# AddOnCard.net
KiCad netlist of a schematic drawn in Altium Designer
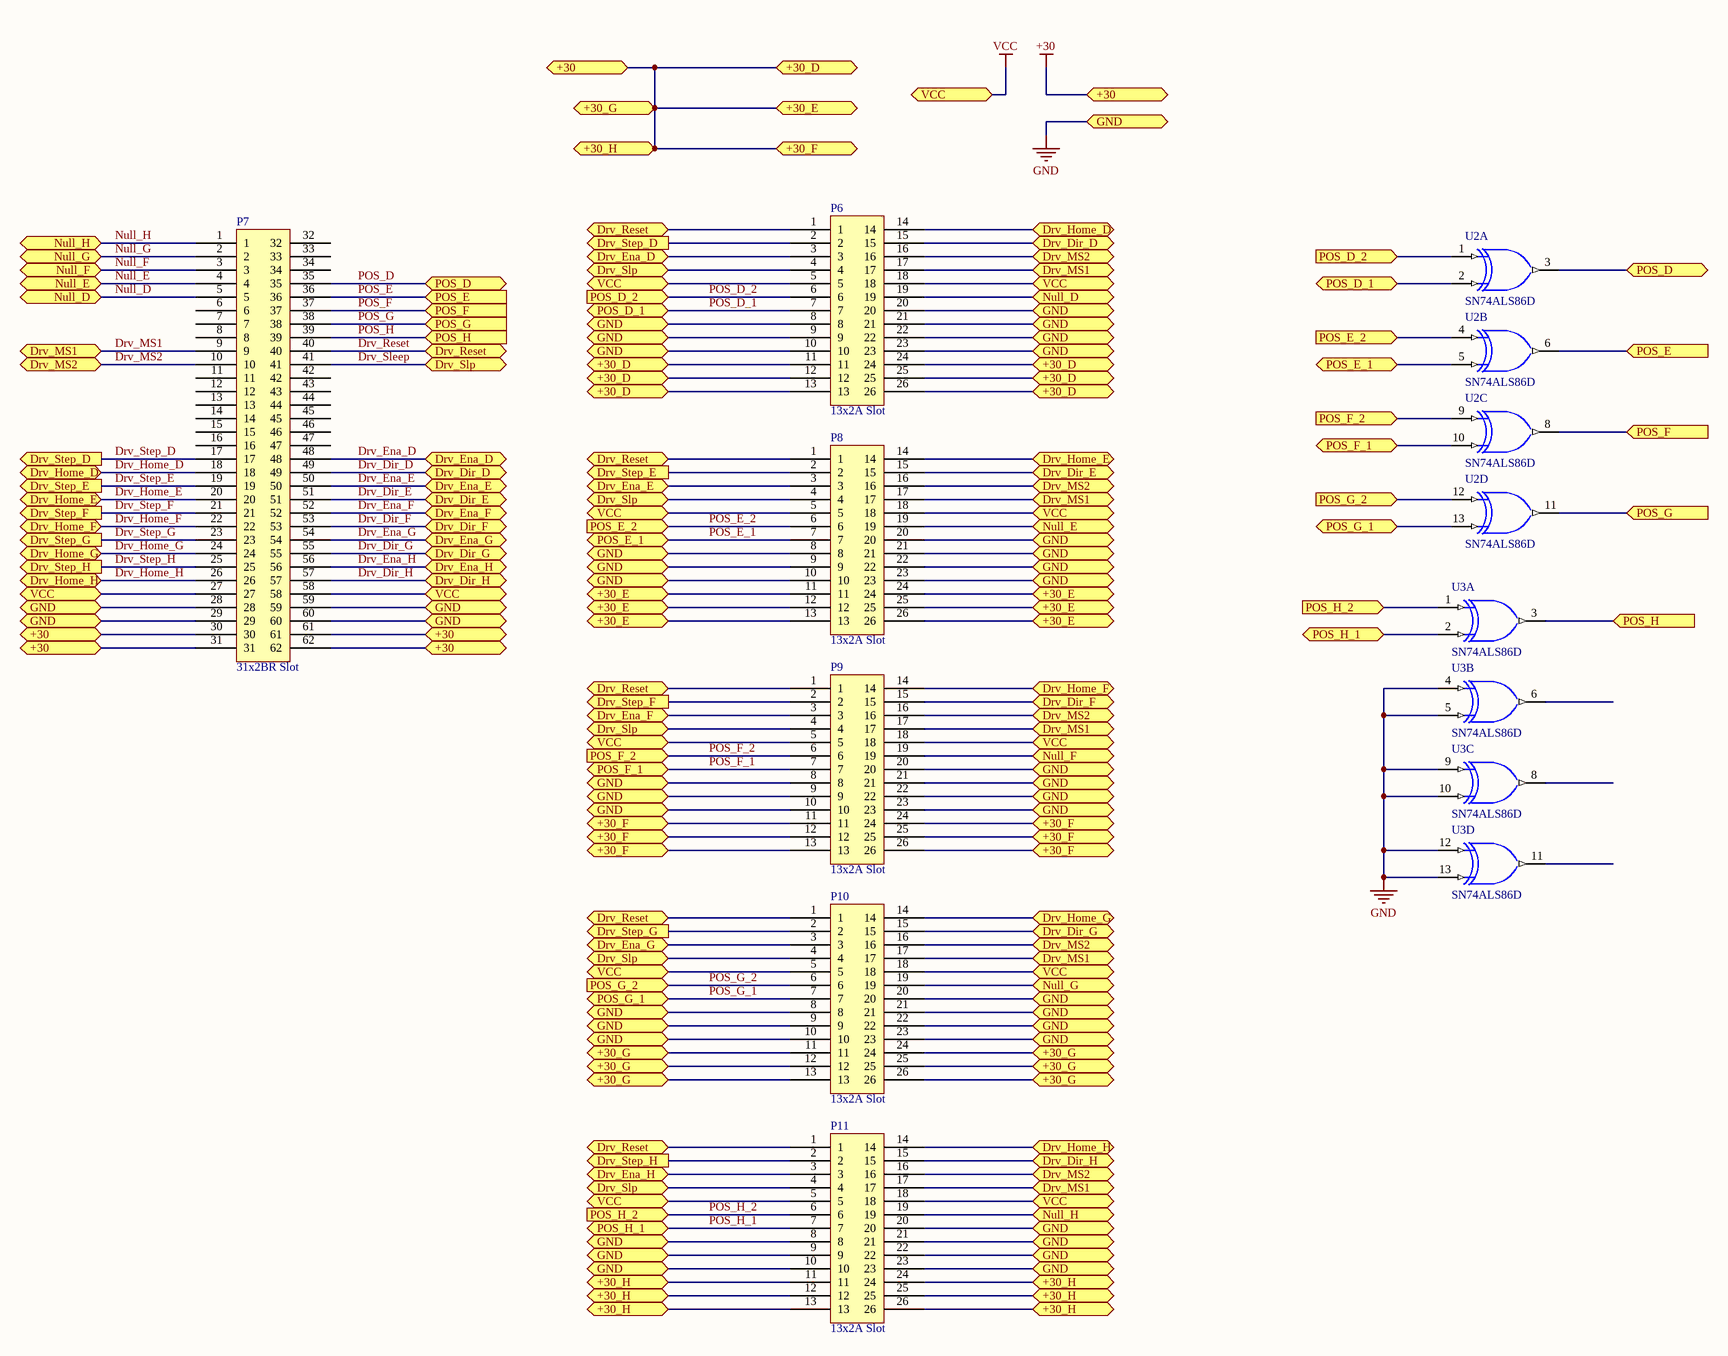
[diagram p0: AddOnCard.SchDoc]

(export (version "E")
  (design (tool "Eeschema 10.0.6"))
  (components
    (comp (ref "P6") (value "13x2A Slot") (footprint "SL-26A") (libsource (lib "Slot") (part "13x2A Slot")))
    (comp (ref "P7")
      (value "31x2BR Slot")
      (footprint "SL-62BR")
      (description "31x2 Slot")
      (libsource (lib "Slot") (part "31x2BR Slot"))
    )
    (comp (ref "P8") (value "13x2A Slot") (footprint "SL-26A") (libsource (lib "Slot") (part "13x2A Slot")))
    (comp (ref "P9") (value "13x2A Slot") (footprint "SL-26A") (libsource (lib "Slot") (part "13x2A Slot")))
    (comp (ref "P10") (value "13x2A Slot") (footprint "SL-26A") (libsource (lib "Slot") (part "13x2A Slot")))
    (comp (ref "P11") (value "13x2A Slot") (footprint "SL-26A") (libsource (lib "Slot") (part "13x2A Slot")))
    (comp (ref "U2")
      (value "SN74ALS86D")
      (footprint "D014_N")
      (description "Quadruple 2-Input Exclusive-OR Gate")
      (fields (field (name "PUBLISHER") "Altium Limited"))
      (libsource (lib "TI Logic Gate 1") (part "SN74ALS86D"))
    )
    (comp (ref "U3")
      (value "SN74ALS86D")
      (footprint "D014_N")
      (description "Quadruple 2-Input Exclusive-OR Gate")
      (fields (field (name "PUBLISHER") "Altium Limited"))
      (libsource (lib "TI Logic Gate 1") (part "SN74ALS86D"))
    )
  )
  (nets
    (net (code "1") (name "+30") (class "Default")
      (node (ref "P10") (pin "11") (pinfunction "11_11") (pintype "passive"))
      (node (ref "P10") (pin "12") (pinfunction "12_12") (pintype "passive"))
      (node (ref "P10") (pin "13") (pinfunction "13_13") (pintype "passive"))
      (node (ref "P10") (pin "24") (pinfunction "24_24") (pintype "passive"))
      (node (ref "P10") (pin "25") (pinfunction "25_25") (pintype "passive"))
      (node (ref "P10") (pin "26") (pinfunction "26_26") (pintype "passive"))
      (node (ref "P11") (pin "11") (pinfunction "11_11") (pintype "passive"))
      (node (ref "P11") (pin "12") (pinfunction "12_12") (pintype "passive"))
      (node (ref "P11") (pin "13") (pinfunction "13_13") (pintype "passive"))
      (node (ref "P11") (pin "24") (pinfunction "24_24") (pintype "passive"))
      (node (ref "P11") (pin "25") (pinfunction "25_25") (pintype "passive"))
      (node (ref "P11") (pin "26") (pinfunction "26_26") (pintype "passive"))
      (node (ref "P6") (pin "11") (pinfunction "11_11") (pintype "passive"))
      (node (ref "P6") (pin "12") (pinfunction "12_12") (pintype "passive"))
      (node (ref "P6") (pin "13") (pinfunction "13_13") (pintype "passive"))
      (node (ref "P6") (pin "24") (pinfunction "24_24") (pintype "passive"))
      (node (ref "P6") (pin "25") (pinfunction "25_25") (pintype "passive"))
      (node (ref "P6") (pin "26") (pinfunction "26_26") (pintype "passive"))
      (node (ref "P7") (pin "30") (pinfunction "30_30") (pintype "passive"))
      (node (ref "P7") (pin "31") (pinfunction "31_31") (pintype "passive"))
      (node (ref "P7") (pin "61") (pinfunction "61_61") (pintype "passive"))
      (node (ref "P7") (pin "62") (pinfunction "62_62") (pintype "passive"))
      (node (ref "P8") (pin "11") (pinfunction "11_11") (pintype "passive"))
      (node (ref "P8") (pin "12") (pinfunction "12_12") (pintype "passive"))
      (node (ref "P8") (pin "13") (pinfunction "13_13") (pintype "passive"))
      (node (ref "P8") (pin "24") (pinfunction "24_24") (pintype "passive"))
      (node (ref "P8") (pin "25") (pinfunction "25_25") (pintype "passive"))
      (node (ref "P8") (pin "26") (pinfunction "26_26") (pintype "passive"))
      (node (ref "P9") (pin "11") (pinfunction "11_11") (pintype "passive"))
      (node (ref "P9") (pin "12") (pinfunction "12_12") (pintype "passive"))
      (node (ref "P9") (pin "13") (pinfunction "13_13") (pintype "passive"))
      (node (ref "P9") (pin "24") (pinfunction "24_24") (pintype "passive"))
      (node (ref "P9") (pin "25") (pinfunction "25_25") (pintype "passive"))
      (node (ref "P9") (pin "26") (pinfunction "26_26") (pintype "passive"))
    )
    (net (code "2") (name "/Drv_Dir_D") (class "Default")
      (node (ref "P6") (pin "15") (pinfunction "15_15") (pintype "passive"))
      (node (ref "P7") (pin "49") (pinfunction "49_49") (pintype "passive"))
    )
    (net (code "3") (name "/Drv_Dir_E") (class "Default")
      (node (ref "P7") (pin "51") (pinfunction "51_51") (pintype "passive"))
      (node (ref "P8") (pin "15") (pinfunction "15_15") (pintype "passive"))
    )
    (net (code "4") (name "/Drv_Dir_F") (class "Default")
      (node (ref "P7") (pin "53") (pinfunction "53_53") (pintype "passive"))
      (node (ref "P9") (pin "15") (pinfunction "15_15") (pintype "passive"))
    )
    (net (code "5") (name "/Drv_Dir_G") (class "Default")
      (node (ref "P10") (pin "15") (pinfunction "15_15") (pintype "passive"))
      (node (ref "P7") (pin "55") (pinfunction "55_55") (pintype "passive"))
    )
    (net (code "6") (name "/Drv_Dir_H") (class "Default")
      (node (ref "P11") (pin "15") (pinfunction "15_15") (pintype "passive"))
      (node (ref "P7") (pin "57") (pinfunction "57_57") (pintype "passive"))
    )
    (net (code "7") (name "/Drv_Ena_D") (class "Default")
      (node (ref "P6") (pin "3") (pinfunction "3_3") (pintype "passive"))
      (node (ref "P7") (pin "48") (pinfunction "48_48") (pintype "passive"))
    )
    (net (code "8") (name "/Drv_Ena_E") (class "Default")
      (node (ref "P7") (pin "50") (pinfunction "50_50") (pintype "passive"))
      (node (ref "P8") (pin "3") (pinfunction "3_3") (pintype "passive"))
    )
    (net (code "9") (name "/Drv_Ena_F") (class "Default")
      (node (ref "P7") (pin "52") (pinfunction "52_52") (pintype "passive"))
      (node (ref "P9") (pin "3") (pinfunction "3_3") (pintype "passive"))
    )
    (net (code "10") (name "/Drv_Ena_G") (class "Default")
      (node (ref "P10") (pin "3") (pinfunction "3_3") (pintype "passive"))
      (node (ref "P7") (pin "54") (pinfunction "54_54") (pintype "passive"))
    )
    (net (code "11") (name "/Drv_Ena_H") (class "Default")
      (node (ref "P11") (pin "3") (pinfunction "3_3") (pintype "passive"))
      (node (ref "P7") (pin "56") (pinfunction "56_56") (pintype "passive"))
    )
    (net (code "12") (name "/Drv_Home_D") (class "Default")
      (node (ref "P6") (pin "14") (pinfunction "14_14") (pintype "passive"))
      (node (ref "P7") (pin "18") (pinfunction "18_18") (pintype "passive"))
    )
    (net (code "13") (name "/Drv_Home_E") (class "Default")
      (node (ref "P7") (pin "20") (pinfunction "20_20") (pintype "passive"))
      (node (ref "P8") (pin "14") (pinfunction "14_14") (pintype "passive"))
    )
    (net (code "14") (name "/Drv_Home_F") (class "Default")
      (node (ref "P7") (pin "22") (pinfunction "22_22") (pintype "passive"))
      (node (ref "P9") (pin "14") (pinfunction "14_14") (pintype "passive"))
    )
    (net (code "15") (name "/Drv_Home_G") (class "Default")
      (node (ref "P10") (pin "14") (pinfunction "14_14") (pintype "passive"))
      (node (ref "P7") (pin "24") (pinfunction "24_24") (pintype "passive"))
    )
    (net (code "16") (name "/Drv_Home_H") (class "Default")
      (node (ref "P11") (pin "14") (pinfunction "14_14") (pintype "passive"))
      (node (ref "P7") (pin "26") (pinfunction "26_26") (pintype "passive"))
    )
    (net (code "17") (name "/Drv_MS1") (class "Default")
      (node (ref "P10") (pin "17") (pinfunction "17_17") (pintype "passive"))
      (node (ref "P11") (pin "17") (pinfunction "17_17") (pintype "passive"))
      (node (ref "P6") (pin "17") (pinfunction "17_17") (pintype "passive"))
      (node (ref "P7") (pin "9") (pinfunction "9_9") (pintype "passive"))
      (node (ref "P8") (pin "17") (pinfunction "17_17") (pintype "passive"))
      (node (ref "P9") (pin "17") (pinfunction "17_17") (pintype "passive"))
    )
    (net (code "18") (name "/Drv_MS2") (class "Default")
      (node (ref "P10") (pin "16") (pinfunction "16_16") (pintype "passive"))
      (node (ref "P11") (pin "16") (pinfunction "16_16") (pintype "passive"))
      (node (ref "P6") (pin "16") (pinfunction "16_16") (pintype "passive"))
      (node (ref "P7") (pin "10") (pinfunction "10_10") (pintype "passive"))
      (node (ref "P8") (pin "16") (pinfunction "16_16") (pintype "passive"))
      (node (ref "P9") (pin "16") (pinfunction "16_16") (pintype "passive"))
    )
    (net (code "19") (name "/Drv_Reset") (class "Default")
      (node (ref "P10") (pin "1") (pinfunction "1_1") (pintype "passive"))
      (node (ref "P11") (pin "1") (pinfunction "1_1") (pintype "passive"))
      (node (ref "P6") (pin "1") (pinfunction "1_1") (pintype "passive"))
      (node (ref "P7") (pin "40") (pinfunction "40_40") (pintype "passive"))
      (node (ref "P8") (pin "1") (pinfunction "1_1") (pintype "passive"))
      (node (ref "P9") (pin "1") (pinfunction "1_1") (pintype "passive"))
    )
    (net (code "20") (name "/Drv_Sleep") (class "Default")
      (node (ref "P10") (pin "4") (pinfunction "4_4") (pintype "passive"))
      (node (ref "P11") (pin "4") (pinfunction "4_4") (pintype "passive"))
      (node (ref "P6") (pin "4") (pinfunction "4_4") (pintype "passive"))
      (node (ref "P7") (pin "41") (pinfunction "41_41") (pintype "passive"))
      (node (ref "P8") (pin "4") (pinfunction "4_4") (pintype "passive"))
      (node (ref "P9") (pin "4") (pinfunction "4_4") (pintype "passive"))
    )
    (net (code "21") (name "/Drv_Step_D") (class "Default")
      (node (ref "P6") (pin "2") (pinfunction "2_2") (pintype "passive"))
      (node (ref "P7") (pin "17") (pinfunction "17_17") (pintype "passive"))
    )
    (net (code "22") (name "/Drv_Step_E") (class "Default")
      (node (ref "P7") (pin "19") (pinfunction "19_19") (pintype "passive"))
      (node (ref "P8") (pin "2") (pinfunction "2_2") (pintype "passive"))
    )
    (net (code "23") (name "/Drv_Step_F") (class "Default")
      (node (ref "P7") (pin "21") (pinfunction "21_21") (pintype "passive"))
      (node (ref "P9") (pin "2") (pinfunction "2_2") (pintype "passive"))
    )
    (net (code "24") (name "/Drv_Step_G") (class "Default")
      (node (ref "P10") (pin "2") (pinfunction "2_2") (pintype "passive"))
      (node (ref "P7") (pin "23") (pinfunction "23_23") (pintype "passive"))
    )
    (net (code "25") (name "/Drv_Step_H") (class "Default")
      (node (ref "P11") (pin "2") (pinfunction "2_2") (pintype "passive"))
      (node (ref "P7") (pin "25") (pinfunction "25_25") (pintype "passive"))
    )
    (net (code "26") (name "/Null_D") (class "Default")
      (node (ref "P6") (pin "19") (pinfunction "19_19") (pintype "passive"))
      (node (ref "P7") (pin "5") (pinfunction "5_5") (pintype "passive"))
    )
    (net (code "27") (name "/Null_E") (class "Default")
      (node (ref "P7") (pin "4") (pinfunction "4_4") (pintype "passive"))
      (node (ref "P8") (pin "19") (pinfunction "19_19") (pintype "passive"))
    )
    (net (code "28") (name "/Null_F") (class "Default")
      (node (ref "P7") (pin "3") (pinfunction "3_3") (pintype "passive"))
      (node (ref "P9") (pin "19") (pinfunction "19_19") (pintype "passive"))
    )
    (net (code "29") (name "/Null_G") (class "Default")
      (node (ref "P10") (pin "19") (pinfunction "19_19") (pintype "passive"))
      (node (ref "P7") (pin "2") (pinfunction "2_2") (pintype "passive"))
    )
    (net (code "30") (name "/Null_H") (class "Default")
      (node (ref "P11") (pin "19") (pinfunction "19_19") (pintype "passive"))
      (node (ref "P7") (pin "1") (pinfunction "1_1") (pintype "passive"))
    )
    (net (code "31") (name "/POS_D") (class "Default")
      (node (ref "P7") (pin "35") (pinfunction "35_35") (pintype "passive"))
      (node (ref "U2") (pin "3") (pinfunction "Y_3") (pintype "output"))
    )
    (net (code "32") (name "/POS_D_1") (class "Default")
      (node (ref "P6") (pin "7") (pinfunction "7_7") (pintype "passive"))
      (node (ref "U2") (pin "2") (pinfunction "B_2") (pintype "input"))
    )
    (net (code "33") (name "/POS_D_2") (class "Default")
      (node (ref "P6") (pin "6") (pinfunction "6_6") (pintype "passive"))
      (node (ref "U2") (pin "1") (pinfunction "A_1") (pintype "input"))
    )
    (net (code "34") (name "/POS_E") (class "Default")
      (node (ref "P7") (pin "36") (pinfunction "36_36") (pintype "passive"))
      (node (ref "U2") (pin "6") (pinfunction "Y_6") (pintype "output"))
    )
    (net (code "35") (name "/POS_E_1") (class "Default")
      (node (ref "P8") (pin "7") (pinfunction "7_7") (pintype "passive"))
      (node (ref "U2") (pin "5") (pinfunction "B_5") (pintype "input"))
    )
    (net (code "36") (name "/POS_E_2") (class "Default")
      (node (ref "P8") (pin "6") (pinfunction "6_6") (pintype "passive"))
      (node (ref "U2") (pin "4") (pinfunction "A_4") (pintype "input"))
    )
    (net (code "37") (name "/POS_F") (class "Default")
      (node (ref "P7") (pin "37") (pinfunction "37_37") (pintype "passive"))
      (node (ref "U2") (pin "8") (pinfunction "Y_8") (pintype "output"))
    )
    (net (code "38") (name "/POS_F_1") (class "Default")
      (node (ref "P9") (pin "7") (pinfunction "7_7") (pintype "passive"))
      (node (ref "U2") (pin "10") (pinfunction "B_10") (pintype "input"))
    )
    (net (code "39") (name "/POS_F_2") (class "Default")
      (node (ref "P9") (pin "6") (pinfunction "6_6") (pintype "passive"))
      (node (ref "U2") (pin "9") (pinfunction "A_9") (pintype "input"))
    )
    (net (code "40") (name "/POS_G") (class "Default")
      (node (ref "P7") (pin "38") (pinfunction "38_38") (pintype "passive"))
      (node (ref "U2") (pin "11") (pinfunction "Y_11") (pintype "output"))
    )
    (net (code "41") (name "/POS_G_1") (class "Default")
      (node (ref "P10") (pin "7") (pinfunction "7_7") (pintype "passive"))
      (node (ref "U2") (pin "13") (pinfunction "B_13") (pintype "input"))
    )
    (net (code "42") (name "/POS_G_2") (class "Default")
      (node (ref "P10") (pin "6") (pinfunction "6_6") (pintype "passive"))
      (node (ref "U2") (pin "12") (pinfunction "A_12") (pintype "input"))
    )
    (net (code "43") (name "/POS_H") (class "Default")
      (node (ref "P7") (pin "39") (pinfunction "39_39") (pintype "passive"))
      (node (ref "U3") (pin "3") (pinfunction "Y_3") (pintype "output"))
    )
    (net (code "44") (name "/POS_H_1") (class "Default")
      (node (ref "P11") (pin "7") (pinfunction "7_7") (pintype "passive"))
      (node (ref "U3") (pin "2") (pinfunction "B_2") (pintype "input"))
    )
    (net (code "45") (name "/POS_H_2") (class "Default")
      (node (ref "P11") (pin "6") (pinfunction "6_6") (pintype "passive"))
      (node (ref "U3") (pin "1") (pinfunction "A_1") (pintype "input"))
    )
    (net (code "46") (name "GND") (class "Default")
      (node (ref "P10") (pin "10") (pinfunction "10_10") (pintype "passive"))
      (node (ref "P10") (pin "20") (pinfunction "20_20") (pintype "passive"))
      (node (ref "P10") (pin "21") (pinfunction "21_21") (pintype "passive"))
      (node (ref "P10") (pin "22") (pinfunction "22_22") (pintype "passive"))
      (node (ref "P10") (pin "23") (pinfunction "23_23") (pintype "passive"))
      (node (ref "P10") (pin "8") (pinfunction "8_8") (pintype "passive"))
      (node (ref "P10") (pin "9") (pinfunction "9_9") (pintype "passive"))
      (node (ref "P11") (pin "10") (pinfunction "10_10") (pintype "passive"))
      (node (ref "P11") (pin "20") (pinfunction "20_20") (pintype "passive"))
      (node (ref "P11") (pin "21") (pinfunction "21_21") (pintype "passive"))
      (node (ref "P11") (pin "22") (pinfunction "22_22") (pintype "passive"))
      (node (ref "P11") (pin "23") (pinfunction "23_23") (pintype "passive"))
      (node (ref "P11") (pin "8") (pinfunction "8_8") (pintype "passive"))
      (node (ref "P11") (pin "9") (pinfunction "9_9") (pintype "passive"))
      (node (ref "P6") (pin "10") (pinfunction "10_10") (pintype "passive"))
      (node (ref "P6") (pin "20") (pinfunction "20_20") (pintype "passive"))
      (node (ref "P6") (pin "21") (pinfunction "21_21") (pintype "passive"))
      (node (ref "P6") (pin "22") (pinfunction "22_22") (pintype "passive"))
      (node (ref "P6") (pin "23") (pinfunction "23_23") (pintype "passive"))
      (node (ref "P6") (pin "8") (pinfunction "8_8") (pintype "passive"))
      (node (ref "P6") (pin "9") (pinfunction "9_9") (pintype "passive"))
      (node (ref "P7") (pin "28") (pinfunction "28_28") (pintype "passive"))
      (node (ref "P7") (pin "29") (pinfunction "29_29") (pintype "passive"))
      (node (ref "P7") (pin "59") (pinfunction "59_59") (pintype "passive"))
      (node (ref "P7") (pin "60") (pinfunction "60_60") (pintype "passive"))
      (node (ref "P8") (pin "10") (pinfunction "10_10") (pintype "passive"))
      (node (ref "P8") (pin "20") (pinfunction "20_20") (pintype "passive"))
      (node (ref "P8") (pin "21") (pinfunction "21_21") (pintype "passive"))
      (node (ref "P8") (pin "22") (pinfunction "22_22") (pintype "passive"))
      (node (ref "P8") (pin "23") (pinfunction "23_23") (pintype "passive"))
      (node (ref "P8") (pin "8") (pinfunction "8_8") (pintype "passive"))
      (node (ref "P8") (pin "9") (pinfunction "9_9") (pintype "passive"))
      (node (ref "P9") (pin "10") (pinfunction "10_10") (pintype "passive"))
      (node (ref "P9") (pin "20") (pinfunction "20_20") (pintype "passive"))
      (node (ref "P9") (pin "21") (pinfunction "21_21") (pintype "passive"))
      (node (ref "P9") (pin "22") (pinfunction "22_22") (pintype "passive"))
      (node (ref "P9") (pin "23") (pinfunction "23_23") (pintype "passive"))
      (node (ref "P9") (pin "8") (pinfunction "8_8") (pintype "passive"))
      (node (ref "P9") (pin "9") (pinfunction "9_9") (pintype "passive"))
      (node (ref "U2") (pin "7") (pinfunction "GND_7") (pintype "power_in"))
      (node (ref "U3") (pin "10") (pinfunction "B_10") (pintype "input"))
      (node (ref "U3") (pin "12") (pinfunction "A_12") (pintype "input"))
      (node (ref "U3") (pin "13") (pinfunction "B_13") (pintype "input"))
      (node (ref "U3") (pin "4") (pinfunction "A_4") (pintype "input"))
      (node (ref "U3") (pin "5") (pinfunction "B_5") (pintype "input"))
      (node (ref "U3") (pin "7") (pinfunction "GND_7") (pintype "power_in"))
      (node (ref "U3") (pin "9") (pinfunction "A_9") (pintype "input"))
    )
    (net (code "47") (name "VCC") (class "Default")
      (node (ref "P10") (pin "18") (pinfunction "18_18") (pintype "passive"))
      (node (ref "P10") (pin "5") (pinfunction "5_5") (pintype "passive"))
      (node (ref "P11") (pin "18") (pinfunction "18_18") (pintype "passive"))
      (node (ref "P11") (pin "5") (pinfunction "5_5") (pintype "passive"))
      (node (ref "P6") (pin "18") (pinfunction "18_18") (pintype "passive"))
      (node (ref "P6") (pin "5") (pinfunction "5_5") (pintype "passive"))
      (node (ref "P7") (pin "27") (pinfunction "27_27") (pintype "passive"))
      (node (ref "P7") (pin "58") (pinfunction "58_58") (pintype "passive"))
      (node (ref "P8") (pin "18") (pinfunction "18_18") (pintype "passive"))
      (node (ref "P8") (pin "5") (pinfunction "5_5") (pintype "passive"))
      (node (ref "P9") (pin "18") (pinfunction "18_18") (pintype "passive"))
      (node (ref "P9") (pin "5") (pinfunction "5_5") (pintype "passive"))
      (node (ref "U2") (pin "14") (pinfunction "VCC_14") (pintype "power_in"))
      (node (ref "U3") (pin "14") (pinfunction "VCC_14") (pintype "power_in"))
    )
    (net (code "48") (name "unconnected-(P7-Pad6)") (class "Default")
      (node (ref "P7") (pin "6") (pinfunction "6_6") (pintype "passive"))
    )
    (net (code "49") (name "unconnected-(P7-Pad7)") (class "Default")
      (node (ref "P7") (pin "7") (pinfunction "7_7") (pintype "passive"))
    )
    (net (code "50") (name "unconnected-(P7-Pad8)") (class "Default")
      (node (ref "P7") (pin "8") (pinfunction "8_8") (pintype "passive"))
    )
    (net (code "51") (name "unconnected-(P7-Pad11)") (class "Default")
      (node (ref "P7") (pin "11") (pinfunction "11_11") (pintype "passive"))
    )
    (net (code "52") (name "unconnected-(P7-Pad12)") (class "Default")
      (node (ref "P7") (pin "12") (pinfunction "12_12") (pintype "passive"))
    )
    (net (code "53") (name "unconnected-(P7-Pad13)") (class "Default")
      (node (ref "P7") (pin "13") (pinfunction "13_13") (pintype "passive"))
    )
    (net (code "54") (name "unconnected-(P7-Pad14)") (class "Default")
      (node (ref "P7") (pin "14") (pinfunction "14_14") (pintype "passive"))
    )
    (net (code "55") (name "unconnected-(P7-Pad15)") (class "Default")
      (node (ref "P7") (pin "15") (pinfunction "15_15") (pintype "passive"))
    )
    (net (code "56") (name "unconnected-(P7-Pad16)") (class "Default")
      (node (ref "P7") (pin "16") (pinfunction "16_16") (pintype "passive"))
    )
    (net (code "57") (name "unconnected-(P7-Pad32)") (class "Default")
      (node (ref "P7") (pin "32") (pinfunction "32_32") (pintype "passive"))
    )
    (net (code "58") (name "unconnected-(P7-Pad33)") (class "Default")
      (node (ref "P7") (pin "33") (pinfunction "33_33") (pintype "passive"))
    )
    (net (code "59") (name "unconnected-(P7-Pad34)") (class "Default")
      (node (ref "P7") (pin "34") (pinfunction "34_34") (pintype "passive"))
    )
    (net (code "60") (name "unconnected-(P7-Pad42)") (class "Default")
      (node (ref "P7") (pin "42") (pinfunction "42_42") (pintype "passive"))
    )
    (net (code "61") (name "unconnected-(P7-Pad43)") (class "Default")
      (node (ref "P7") (pin "43") (pinfunction "43_43") (pintype "passive"))
    )
    (net (code "62") (name "unconnected-(P7-Pad44)") (class "Default")
      (node (ref "P7") (pin "44") (pinfunction "44_44") (pintype "passive"))
    )
    (net (code "63") (name "unconnected-(P7-Pad45)") (class "Default")
      (node (ref "P7") (pin "45") (pinfunction "45_45") (pintype "passive"))
    )
    (net (code "64") (name "unconnected-(P7-Pad46)") (class "Default")
      (node (ref "P7") (pin "46") (pinfunction "46_46") (pintype "passive"))
    )
    (net (code "65") (name "unconnected-(P7-Pad47)") (class "Default")
      (node (ref "P7") (pin "47") (pinfunction "47_47") (pintype "passive"))
    )
    (net (code "66") (name "unconnected-(U3B-Y-Pad6)") (class "Default")
      (node (ref "U3") (pin "6") (pinfunction "Y_6") (pintype "output"))
    )
    (net (code "67") (name "unconnected-(U3C-Y-Pad8)") (class "Default")
      (node (ref "U3") (pin "8") (pinfunction "Y_8") (pintype "output"))
    )
    (net (code "68") (name "unconnected-(U3D-Y-Pad11)") (class "Default")
      (node (ref "U3") (pin "11") (pinfunction "Y_11") (pintype "output"))
    )
  )
)
